# SAMD21.net
KiCad netlist of a schematic drawn in Altium Designer
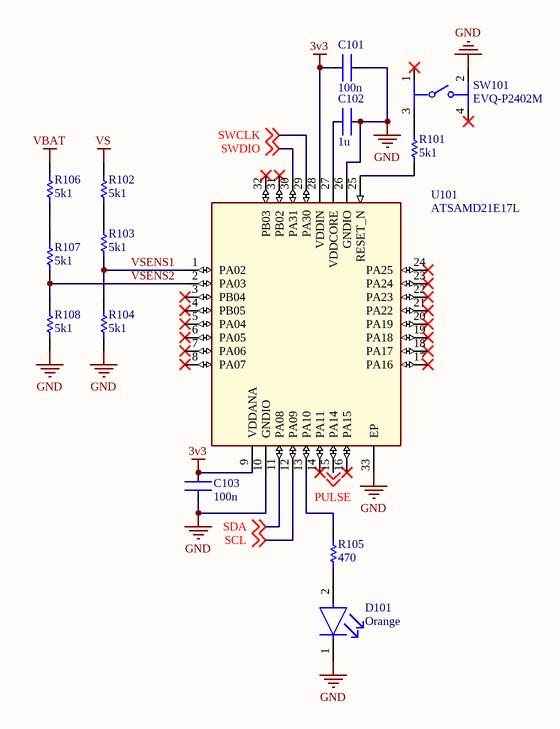
[diagram p0: SAMD21.SchDoc]

(export (version "E")
  (design (tool "Eeschema 10.0.6"))
  (components
    (comp (ref "C101")
      (value "100n")
      (footprint "FP-GCM155-0_05-MFG")
      (description "Ceramic Capacitor for Automotive 100nF ±10% 50VDC X7R 0402 Paper T/R")
      (fields (field (name "TOLERANCE") "10%"))
      (libsource (lib "Main") (part "GCM155R71H104KE02J"))
    )
    (comp (ref "C102")
      (value "1u")
      (footprint "FP-GRM155-0_1-MFG")
      (description "Chip Multilayer Ceramic Capacitors for General Purpose, 0402, 1.0uF, X5R, 15%, 20%, 50V")
      (libsource (lib "Main") (part "GRM155R61H105ME05D"))
    )
    (comp (ref "C103")
      (value "100n")
      (footprint "FP-GCM155-0_05-MFG")
      (description "Ceramic Capacitor for Automotive 100nF ±10% 50VDC X7R 0402 Paper T/R")
      (fields (field (name "TOLERANCE") "10%"))
      (libsource (lib "Main") (part "GCM155R71H104KE02J"))
    )
    (comp (ref "D101")
      (value "Orange")
      (footprint "FP-SML-P1-MFG")
      (description "LED ORANGE CLEAR 1006 SMD")
      (fields
        (field (name "MANUFACTURER PART NUMBER") "SML-P11DTT86R")
        (field (name "OCTOPART") "https://octopart.com/sml-p11dtt86r-rohm-34112313")
      )
      (libsource (lib "Main") (part "SML-P11DTT86R"))
    )
    (comp (ref "R101")
      (value "5k1")
      (footprint "RESC1005X04N")
      (fields (field (name "MANUFACTURER") "Panasonic") (field (name "PART NUMBER") "ERJ2RKF27R0X"))
      (libsource (lib "Main") (part "ERJ-U02J512X"))
    )
    (comp (ref "R102")
      (value "5k1")
      (footprint "RESC1005X04N")
      (fields (field (name "MANUFACTURER") "Panasonic") (field (name "PART NUMBER") "ERJ2RKF27R0X"))
      (libsource (lib "Main") (part "ERJ-U02J512X"))
    )
    (comp (ref "R103")
      (value "5k1")
      (footprint "RESC1005X04N")
      (fields (field (name "MANUFACTURER") "Panasonic") (field (name "PART NUMBER") "ERJ2RKF27R0X"))
      (libsource (lib "Main") (part "ERJ-U02J512X"))
    )
    (comp (ref "R104")
      (value "5k1")
      (footprint "RESC1005X04N")
      (fields (field (name "MANUFACTURER") "Panasonic") (field (name "PART NUMBER") "ERJ2RKF27R0X"))
      (libsource (lib "Main") (part "ERJ-U02J512X"))
    )
    (comp (ref "R105")
      (value "470")
      (footprint "RESC1005X04N")
      (fields (field (name "MANUFACTURER") "Panasonic") (field (name "PART NUMBER") "ERJ2RKF27R0X"))
      (libsource (lib "Main") (part "ERJ-U02J471X"))
    )
    (comp (ref "R106")
      (value "5k1")
      (footprint "RESC1005X04N")
      (fields (field (name "MANUFACTURER") "Panasonic") (field (name "PART NUMBER") "ERJ2RKF27R0X"))
      (libsource (lib "Main") (part "ERJ-U02J512X"))
    )
    (comp (ref "R107")
      (value "5k1")
      (footprint "RESC1005X04N")
      (fields (field (name "MANUFACTURER") "Panasonic") (field (name "PART NUMBER") "ERJ2RKF27R0X"))
      (libsource (lib "Main") (part "ERJ-U02J512X"))
    )
    (comp (ref "R108")
      (value "5k1")
      (footprint "RESC1005X04N")
      (fields (field (name "MANUFACTURER") "Panasonic") (field (name "PART NUMBER") "ERJ2RKF27R0X"))
      (libsource (lib "Main") (part "ERJ-U02J512X"))
    )
    (comp (ref "SW101")
      (value "EVQ-P2402M")
      (footprint "EVQ-P2402M")
      (libsource (lib "Main") (part "EVQ-P2402M"))
    )
    (comp (ref "U101")
      (value "ATSAMD21E17L")
      (footprint "QFN50P500X500X100_HS-33L")
      (libsource (lib "Main") (part "ATSAMD21E17L"))
    )
  )
  (nets
    (net (code "1") (name "/VSENS1") (class "Default")
      (node (ref "R103") (pin "1") (pinfunction "1_1") (pintype "passive"))
      (node (ref "R104") (pin "2") (pinfunction "2_2") (pintype "passive"))
      (node (ref "U101") (pin "1") (pinfunction "PA02_1") (pintype "bidirectional"))
    )
    (net (code "2") (name "/VSENS2") (class "Default")
      (node (ref "R107") (pin "1") (pinfunction "1_1") (pintype "passive"))
      (node (ref "R108") (pin "2") (pinfunction "2_2") (pintype "passive"))
      (node (ref "U101") (pin "2") (pinfunction "PA03_2") (pintype "bidirectional"))
    )
    (net (code "3") (name "3v3") (class "Default")
      (node (ref "C101") (pin "1") (pinfunction "1_1") (pintype "passive"))
      (node (ref "C103") (pin "2") (pinfunction "2_2") (pintype "passive"))
      (node (ref "U101") (pin "28") (pinfunction "VDDIN_28") (pintype "power_in"))
      (node (ref "U101") (pin "9") (pinfunction "VDDANA_9") (pintype "power_in"))
    )
    (net (code "4") (name "GND") (class "Default")
      (node (ref "C101") (pin "2") (pinfunction "2_2") (pintype "passive"))
      (node (ref "C102") (pin "2") (pinfunction "2_2") (pintype "passive"))
      (node (ref "C103") (pin "1") (pinfunction "1_1") (pintype "passive"))
      (node (ref "D101") (pin "1") (pinfunction "C_1") (pintype "passive"))
      (node (ref "R104") (pin "1") (pinfunction "1_1") (pintype "passive"))
      (node (ref "R108") (pin "1") (pinfunction "1_1") (pintype "passive"))
      (node (ref "SW101") (pin "2") (pinfunction "2_2") (pintype "passive"))
      (node (ref "U101") (pin "10") (pinfunction "GNDIO_10") (pintype "power_in"))
      (node (ref "U101") (pin "26") (pinfunction "GNDIO_26") (pintype "power_in"))
      (node (ref "U101") (pin "33") (pinfunction "EP_33") (pintype "power_in"))
    )
    (net (code "5") (name "Net-(D101-A)") (class "Default")
      (node (ref "D101") (pin "2") (pinfunction "A_2") (pintype "passive"))
      (node (ref "R105") (pin "2") (pinfunction "2_2") (pintype "passive"))
    )
    (net (code "6") (name "Net-(R101-Pad1)") (class "Default")
      (node (ref "R101") (pin "1") (pinfunction "1_1") (pintype "passive"))
      (node (ref "SW101") (pin "3") (pinfunction "3_3") (pintype "passive"))
    )
    (net (code "7") (name "Net-(R102-Pad1)") (class "Default")
      (node (ref "R102") (pin "1") (pinfunction "1_1") (pintype "passive"))
      (node (ref "R103") (pin "2") (pinfunction "2_2") (pintype "passive"))
    )
    (net (code "8") (name "Net-(R106-Pad1)") (class "Default")
      (node (ref "R106") (pin "1") (pinfunction "1_1") (pintype "passive"))
      (node (ref "R107") (pin "2") (pinfunction "2_2") (pintype "passive"))
    )
    (net (code "9") (name "Net-(U101-PA10)") (class "Default")
      (node (ref "R105") (pin "1") (pinfunction "1_1") (pintype "passive"))
      (node (ref "U101") (pin "13") (pinfunction "PA10_13") (pintype "bidirectional"))
    )
    (net (code "10") (name "Net-(U101-RESET_N)") (class "Default")
      (node (ref "R101") (pin "2") (pinfunction "2_2") (pintype "passive"))
      (node (ref "U101") (pin "25") (pinfunction "RESET_N_25") (pintype "input"))
    )
    (net (code "11") (name "Net-(U101-VDDCORE)") (class "Default")
      (node (ref "C102") (pin "1") (pinfunction "1_1") (pintype "passive"))
      (node (ref "U101") (pin "27") (pinfunction "VDDCORE_27") (pintype "power_in"))
    )
    (net (code "12") (name "PULSE") (class "Default")
      (node (ref "U101") (pin "15") (pinfunction "PA14_15") (pintype "bidirectional"))
    )
    (net (code "13") (name "SCL") (class "Default")
      (node (ref "U101") (pin "12") (pinfunction "PA09_12") (pintype "bidirectional"))
    )
    (net (code "14") (name "SDA") (class "Default")
      (node (ref "U101") (pin "11") (pinfunction "PA08_11") (pintype "bidirectional"))
    )
    (net (code "15") (name "SWCLK") (class "Default")
      (node (ref "U101") (pin "29") (pinfunction "PA30_29") (pintype "bidirectional"))
    )
    (net (code "16") (name "SWDIO") (class "Default")
      (node (ref "U101") (pin "30") (pinfunction "PA31_30") (pintype "bidirectional"))
    )
    (net (code "17") (name "VBAT") (class "Default")
      (node (ref "R106") (pin "2") (pinfunction "2_2") (pintype "passive"))
    )
    (net (code "18") (name "VS") (class "Default")
      (node (ref "R102") (pin "2") (pinfunction "2_2") (pintype "passive"))
    )
    (net (code "19") (name "unconnected-(SW101-Pad1)") (class "Default")
      (node (ref "SW101") (pin "1") (pinfunction "1_1") (pintype "passive+no_connect"))
    )
    (net (code "20") (name "unconnected-(SW101-Pad4)") (class "Default")
      (node (ref "SW101") (pin "4") (pinfunction "4_4") (pintype "passive+no_connect"))
    )
    (net (code "21") (name "unconnected-(U101-PA04-Pad5)") (class "Default")
      (node (ref "U101") (pin "5") (pinfunction "PA04_5") (pintype "bidirectional+no_connect"))
    )
    (net (code "22") (name "unconnected-(U101-PA05-Pad6)") (class "Default")
      (node (ref "U101") (pin "6") (pinfunction "PA05_6") (pintype "bidirectional+no_connect"))
    )
    (net (code "23") (name "unconnected-(U101-PA06-Pad7)") (class "Default")
      (node (ref "U101") (pin "7") (pinfunction "PA06_7") (pintype "bidirectional+no_connect"))
    )
    (net (code "24") (name "unconnected-(U101-PA07-Pad8)") (class "Default")
      (node (ref "U101") (pin "8") (pinfunction "PA07_8") (pintype "bidirectional+no_connect"))
    )
    (net (code "25") (name "unconnected-(U101-PA11-Pad14)") (class "Default")
      (node (ref "U101") (pin "14") (pinfunction "PA11_14") (pintype "bidirectional+no_connect"))
    )
    (net (code "26") (name "unconnected-(U101-PA15-Pad16)") (class "Default")
      (node (ref "U101") (pin "16") (pinfunction "PA15_16") (pintype "bidirectional+no_connect"))
    )
    (net (code "27") (name "unconnected-(U101-PA16-Pad17)") (class "Default")
      (node (ref "U101") (pin "17") (pinfunction "PA16_17") (pintype "bidirectional+no_connect"))
    )
    (net (code "28") (name "unconnected-(U101-PA17-Pad18)") (class "Default")
      (node (ref "U101") (pin "18") (pinfunction "PA17_18") (pintype "bidirectional+no_connect"))
    )
    (net (code "29") (name "unconnected-(U101-PA18-Pad19)") (class "Default")
      (node (ref "U101") (pin "19") (pinfunction "PA18_19") (pintype "bidirectional+no_connect"))
    )
    (net (code "30") (name "unconnected-(U101-PA19-Pad20)") (class "Default")
      (node (ref "U101") (pin "20") (pinfunction "PA19_20") (pintype "bidirectional+no_connect"))
    )
    (net (code "31") (name "unconnected-(U101-PA22-Pad21)") (class "Default")
      (node (ref "U101") (pin "21") (pinfunction "PA22_21") (pintype "bidirectional+no_connect"))
    )
    (net (code "32") (name "unconnected-(U101-PA23-Pad22)") (class "Default")
      (node (ref "U101") (pin "22") (pinfunction "PA23_22") (pintype "bidirectional+no_connect"))
    )
    (net (code "33") (name "unconnected-(U101-PA24-Pad23)") (class "Default")
      (node (ref "U101") (pin "23") (pinfunction "PA24_23") (pintype "bidirectional+no_connect"))
    )
    (net (code "34") (name "unconnected-(U101-PA25-Pad24)") (class "Default")
      (node (ref "U101") (pin "24") (pinfunction "PA25_24") (pintype "bidirectional+no_connect"))
    )
    (net (code "35") (name "unconnected-(U101-PB02-Pad31)") (class "Default")
      (node (ref "U101") (pin "31") (pinfunction "PB02_31") (pintype "bidirectional+no_connect"))
    )
    (net (code "36") (name "unconnected-(U101-PB03-Pad32)") (class "Default")
      (node (ref "U101") (pin "32") (pinfunction "PB03_32") (pintype "bidirectional+no_connect"))
    )
    (net (code "37") (name "unconnected-(U101-PB04-Pad3)") (class "Default")
      (node (ref "U101") (pin "3") (pinfunction "PB04_3") (pintype "bidirectional+no_connect"))
    )
    (net (code "38") (name "unconnected-(U101-PB05-Pad4)") (class "Default")
      (node (ref "U101") (pin "4") (pinfunction "PB05_4") (pintype "bidirectional+no_connect"))
    )
  )
)
